# auto_threader.net
KiCad netlist of a schematic drawn in Altium Designer
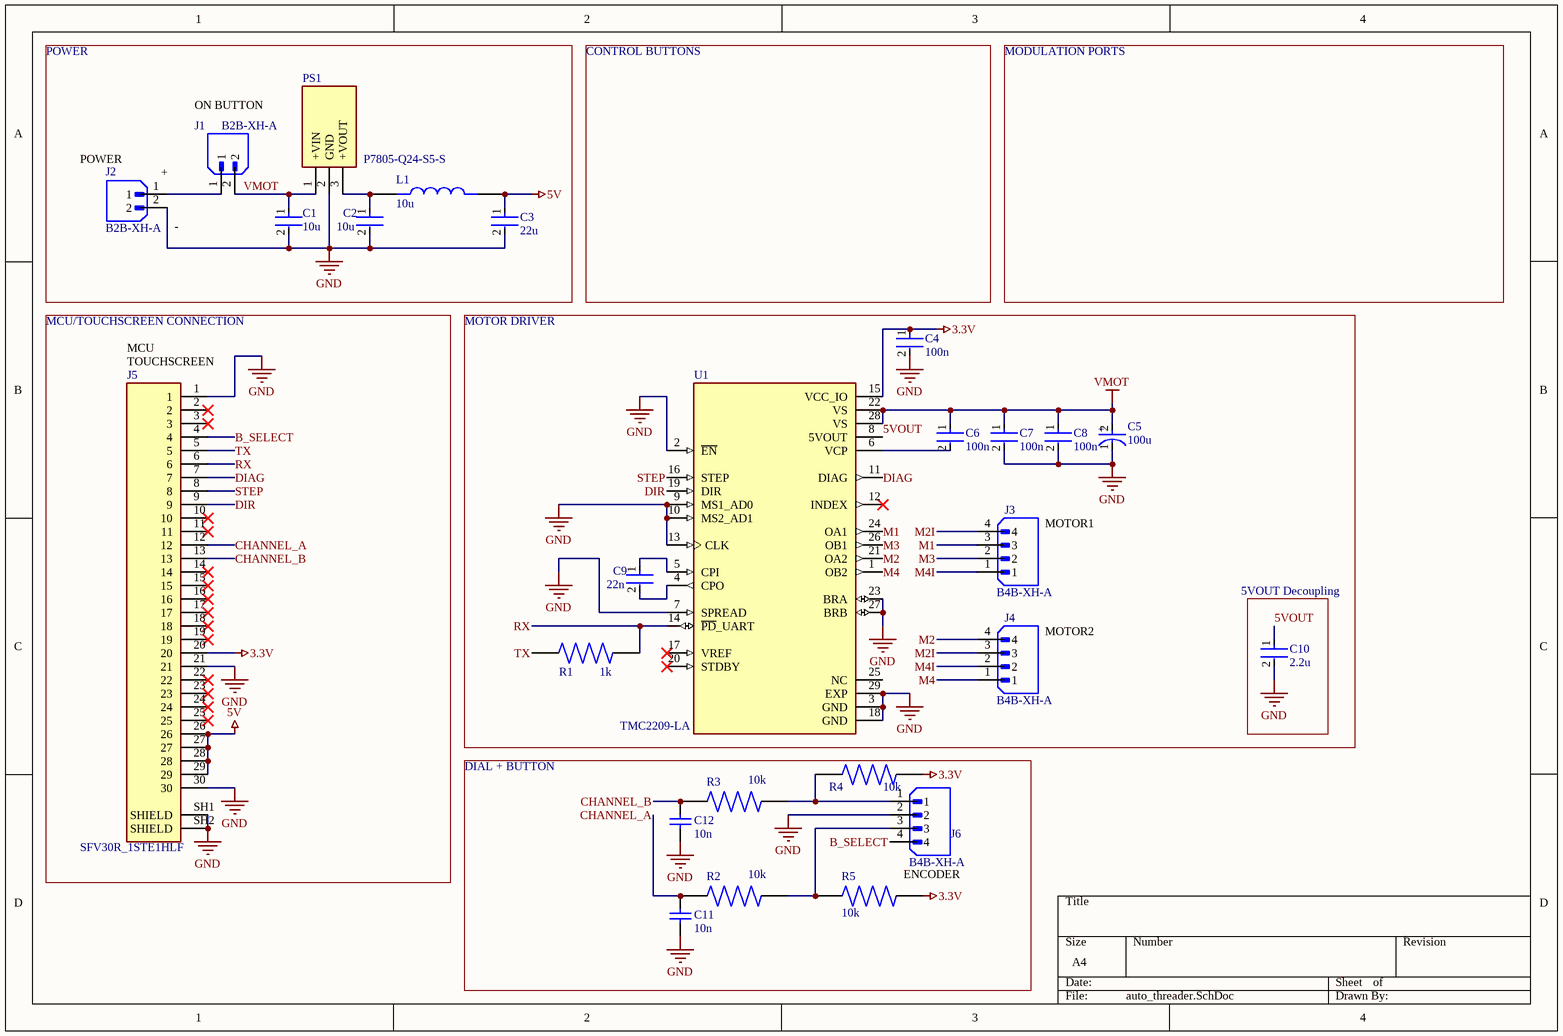
[diagram p0: auto_threader.SchDoc]

(export (version "E")
  (design (tool "Eeschema 10.0.6"))
  (components
    (comp (ref "C1")
      (value "10u")
      (footprint "GRM21BR61H106KE43L")
      (description "50V 10uF X5R ±10% 0805 Multilayer Ceramic Capacitors MLCC - SMD/SMT ROHS")
      (fields
        (field (name "MANUFACTURER") "Murata")
        (field (name "MANUFACTURER PART NUMBER") "GRM21BR61H106KE43L")
      )
      (libsource (lib "auto_threader_lib") (part "GRM21BR61H106KE43L"))
    )
    (comp (ref "C2")
      (value "10u")
      (footprint "GRM21BR71A106KA73L")
      (description "Chip Multilayer Ceramic Capacitors for General Purpose, 0805, 10uF, X7R, 15%, 10%, 10V")
      (fields (field (name "TOLERANCE") "10%"))
      (libsource (lib "auto_threader_lib") (part "GRM21BR71A106KA73L"))
    )
    (comp (ref "C3")
      (value "22u")
      (footprint "GRM188R61A226ME15D")
      (description "10V 22uF X5R ±20% 0603 Multilayer Ceramic Capacitors MLCC - SMD/SMT ROHS")
      (fields
        (field (name "MANUFACTURER") "Murata")
        (field (name "MANUFACTURER PART NUMBER") "GRM188R61A226ME15D")
      )
      (libsource (lib "auto_threader_lib") (part "GRM188R61A226ME15D"))
    )
    (comp (ref "C4")
      (value "100n")
      (footprint "CC0805KRX7R9BB104")
      (description "50V 100nF X7R ±10% 0805 Multilayer Ceramic Capacitors MLCC - SMD/SMT ROHS")
      (fields
        (field (name "MANUFACTURER") "Yageo Group")
        (field (name "MANUFACTURER PART NUMBER") "CC0805KRX7R9BB104")
      )
      (libsource (lib "auto_threader_lib") (part "CC0805KRX7R9BB104"))
    )
    (comp (ref "C5")
      (value "100u")
      (footprint "35ZLH100MEFC6.3X11")
      (description "Aluminum Electrolytic Capacitors-DIP DIP, D6.3xL11mm 100μF ±20% 35V 94mΩ 540mA 6000Hrs@105℃")
      (fields
        (field (name "MANUFACTURER") "Rubycon")
        (field (name "MANUFACTURER PART NUMBER") "35ZLH100MEFC6.3X11")
      )
      (libsource (lib "auto_threader_lib") (part "35ZLH100MEFC6.3X11"))
    )
    (comp (ref "C6")
      (value "100n")
      (footprint "CC0805KRX7R9BB104")
      (description "50V 100nF X7R ±10% 0805 Multilayer Ceramic Capacitors MLCC - SMD/SMT ROHS")
      (fields
        (field (name "MANUFACTURER") "Yageo Group")
        (field (name "MANUFACTURER PART NUMBER") "CC0805KRX7R9BB104")
      )
      (libsource (lib "auto_threader_lib") (part "CC0805KRX7R9BB104"))
    )
    (comp (ref "C7")
      (value "100n")
      (footprint "CC0805KRX7R9BB104")
      (description "50V 100nF X7R ±10% 0805 Multilayer Ceramic Capacitors MLCC - SMD/SMT ROHS")
      (fields
        (field (name "MANUFACTURER") "Yageo Group")
        (field (name "MANUFACTURER PART NUMBER") "CC0805KRX7R9BB104")
      )
      (libsource (lib "auto_threader_lib") (part "CC0805KRX7R9BB104"))
    )
    (comp (ref "C8")
      (value "100n")
      (footprint "CC0805KRX7R9BB104")
      (description "50V 100nF X7R ±10% 0805 Multilayer Ceramic Capacitors MLCC - SMD/SMT ROHS")
      (fields
        (field (name "MANUFACTURER") "Yageo Group")
        (field (name "MANUFACTURER PART NUMBER") "CC0805KRX7R9BB104")
      )
      (libsource (lib "auto_threader_lib") (part "CC0805KRX7R9BB104"))
    )
    (comp (ref "C9")
      (value "22n")
      (footprint "CC0603KRX7R9BB223")
      (description "Surface Mount Ceramic Multilayer Capacitor 0.022uF 10% X7R 50V 0603 Paper T/R")
      (fields
        (field (name "MANUFACTURER") "Yageo Group")
        (field (name "MANUFACTURER PART NUMBER") "CC0603KRX7R9BB223")
      )
      (libsource (lib "auto_threader_lib") (part "CC0603KRX7R9BB223"))
    )
    (comp (ref "C10")
      (value "2.2u")
      (footprint "GRM155C80J225KE95D")
      (description "6.3V 2.2uF X6S ±10% 0402 Multilayer Ceramic Capacitors MLCC - SMD/SMT ROHS")
      (fields
        (field (name "MANUFACTURER") "Murata")
        (field (name "MANUFACTURER PART NUMBER") "GRM155C80J225KE95D")
      )
      (libsource (lib "auto_threader_lib") (part "GRM155C80J225KE95D"))
    )
    (comp (ref "C11")
      (value "10n")
      (footprint "GCM188R71H103KA37D")
      (description "50V 10nF X7R ±10% 0603 Multilayer Ceramic Capacitors MLCC - SMD/SMT ROHS")
      (fields
        (field (name "MANUFACTURER") "Murata")
        (field (name "MANUFACTURER PART NUMBER") "GCM188R71H103KA37D")
      )
      (libsource (lib "auto_threader_lib") (part "GCM188R71H103KA37D"))
    )
    (comp (ref "C12")
      (value "10n")
      (footprint "GCM188R71H103KA37D")
      (description "50V 10nF X7R ±10% 0603 Multilayer Ceramic Capacitors MLCC - SMD/SMT ROHS")
      (fields
        (field (name "MANUFACTURER") "Murata")
        (field (name "MANUFACTURER PART NUMBER") "GCM188R71H103KA37D")
      )
      (libsource (lib "auto_threader_lib") (part "GCM188R71H103KA37D"))
    )
    (comp (ref "J1")
      (value "B2B-XH-A")
      (footprint "B2B-XH-A")
      (description "To ON BUTTON")
      (libsource (lib "auto_threader_lib") (part "B2B-XH-A"))
    )
    (comp (ref "J2")
      (value "B2B-XH-A")
      (footprint "B2B-XH-A")
      (description "To POWER")
      (libsource (lib "") (part "B2B-XH-A_1"))
    )
    (comp (ref "J3")
      (value "B4B-XH-A")
      (footprint "B4B-XH-A")
      (description "To MOTOR COILS")
      (libsource (lib "auto_threader_lib") (part "B4B-XH-A"))
    )
    (comp (ref "J4")
      (value "B4B-XH-A")
      (footprint "B4B-XH-A")
      (description "To MOTOR COILS")
      (libsource (lib "auto_threader_lib") (part "B4B-XH-A"))
    )
    (comp (ref "J5")
      (value "SFV30R_1STE1HLF")
      (footprint "SFV30R-1STE1HLF")
      (libsource (lib "auto_threader_lib") (part "SFV30R_1STE1HLF"))
    )
    (comp (ref "J6")
      (value "B4B-XH-A")
      (footprint "B4B-XH-A")
      (description "To MOTOR COILS")
      (libsource (lib "") (part "B4B-XH-A_1"))
    )
    (comp (ref "L1")
      (value "10u")
      (footprint "SRP4020TA-100M")
      (description "Ind Power Shielded Wirewound 10uH 20% 100KHz Carbonyl Powder 1.8A T/R")
      (fields
        (field (name "MANUFACTURER") "Bourns")
        (field (name "MANUFACTURER PART NUMBER") "SRP4020TA-100M")
      )
      (libsource (lib "auto_threader_lib") (part "SRP4020TA-100M"))
    )
    (comp (ref "PS1")
      (value "P7805-Q24-S5-S")
      (footprint "P7805-Q24-S5-S")
      (libsource (lib "auto_threader_lib") (part "P7805-Q24-S5-S"))
    )
    (comp (ref "R1")
      (value "1k")
      (footprint "RC0805FR-071KL")
      (description "Yageo RC0805FR-071KL SMD Resistor 0603 1k Ohm ±1% Thick Film")
      (fields
        (field (name "MANUFACTURER") "Yageo Group")
        (field (name "MANUFACTURER PART NUMBER") "RC0805FR-071KL")
      )
      (libsource (lib "auto_threader_lib") (part "RC0805FR-071KL"))
    )
    (comp (ref "R2")
      (value "10k")
      (footprint "RC0805FR-0710KL")
      (description "Res General Purpose Thick Film 0805 10k Ohm 1% 1/8W ±100ppm/°C Ceramic Paper T/R")
      (fields
        (field (name "MANUFACTURER") "Yageo Group")
        (field (name "MANUFACTURER PART NUMBER") "RC0805FR-0710KL")
      )
      (libsource (lib "auto_threader_lib") (part "RC0805FR-0710KL"))
    )
    (comp (ref "R3")
      (value "10k")
      (footprint "RC0805FR-0710KL")
      (description "Res General Purpose Thick Film 0805 10k Ohm 1% 1/8W ±100ppm/°C Ceramic Paper T/R")
      (fields
        (field (name "MANUFACTURER") "Yageo Group")
        (field (name "MANUFACTURER PART NUMBER") "RC0805FR-0710KL")
      )
      (libsource (lib "auto_threader_lib") (part "RC0805FR-0710KL"))
    )
    (comp (ref "R4")
      (value "10k")
      (footprint "RC0805FR-0710KL")
      (description "Res General Purpose Thick Film 0805 10k Ohm 1% 1/8W ±100ppm/°C Ceramic Paper T/R")
      (fields
        (field (name "MANUFACTURER") "Yageo Group")
        (field (name "MANUFACTURER PART NUMBER") "RC0805FR-0710KL")
      )
      (libsource (lib "auto_threader_lib") (part "RC0805FR-0710KL"))
    )
    (comp (ref "R5")
      (value "10k")
      (footprint "RC0805FR-0710KL")
      (description "Res General Purpose Thick Film 0805 10k Ohm 1% 1/8W ±100ppm/°C Ceramic Paper T/R")
      (fields
        (field (name "MANUFACTURER") "Yageo Group")
        (field (name "MANUFACTURER PART NUMBER") "RC0805FR-0710KL")
      )
      (libsource (lib "auto_threader_lib") (part "RC0805FR-0710KL"))
    )
    (comp (ref "U1")
      (value "TMC2209-LA")
      (footprint "TMC2209-LA")
      (libsource (lib "auto_threader_lib") (part "TMC2209-LA"))
    )
  )
  (nets
    (net (code "1") (name "/5VOUT") (class "Default")
      (node (ref "C10") (pin "1") (pinfunction "1_1") (pintype "passive"))
      (node (ref "U1") (pin "8") (pinfunction "5VOUT_8") (pintype "power_in"))
    )
    (net (code "2") (name "/B_SELECT") (class "Default")
      (node (ref "J5") (pin "4") (pinfunction "4_4") (pintype "passive"))
      (node (ref "J6") (pin "4") (pinfunction "4_4") (pintype "passive"))
    )
    (net (code "3") (name "/CHANNEL_A") (class "Default")
      (node (ref "C11") (pin "1") (pinfunction "1_1") (pintype "passive"))
      (node (ref "J5") (pin "12") (pinfunction "12_12") (pintype "passive"))
      (node (ref "R2") (pin "1") (pinfunction "1_1") (pintype "passive"))
    )
    (net (code "4") (name "/CHANNEL_B") (class "Default")
      (node (ref "C12") (pin "1") (pinfunction "1_1") (pintype "passive"))
      (node (ref "J5") (pin "13") (pinfunction "13_13") (pintype "passive"))
      (node (ref "R3") (pin "1") (pinfunction "1_1") (pintype "passive"))
    )
    (net (code "5") (name "/DIAG") (class "Default")
      (node (ref "J5") (pin "7") (pinfunction "7_7") (pintype "passive"))
      (node (ref "U1") (pin "11") (pinfunction "DIAG_11") (pintype "output"))
    )
    (net (code "6") (name "/DIR") (class "Default")
      (node (ref "J5") (pin "9") (pinfunction "9_9") (pintype "passive"))
      (node (ref "U1") (pin "19") (pinfunction "DIR_19") (pintype "input"))
    )
    (net (code "7") (name "/M1") (class "Default")
      (node (ref "J3") (pin "3") (pinfunction "3_3") (pintype "passive"))
      (node (ref "U1") (pin "24") (pinfunction "OA1_24") (pintype "output"))
    )
    (net (code "8") (name "/M2") (class "Default")
      (node (ref "J4") (pin "4") (pinfunction "4_4") (pintype "passive"))
      (node (ref "U1") (pin "21") (pinfunction "OA2_21") (pintype "output"))
    )
    (net (code "9") (name "/M2I") (class "Default")
      (node (ref "J3") (pin "4") (pinfunction "4_4") (pintype "passive"))
      (node (ref "J4") (pin "3") (pinfunction "3_3") (pintype "passive"))
    )
    (net (code "10") (name "/M3") (class "Default")
      (node (ref "J3") (pin "2") (pinfunction "2_2") (pintype "passive"))
      (node (ref "U1") (pin "26") (pinfunction "OB1_26") (pintype "output"))
    )
    (net (code "11") (name "/M4") (class "Default")
      (node (ref "J4") (pin "1") (pinfunction "1_1") (pintype "passive"))
      (node (ref "U1") (pin "1") (pinfunction "OB2_1") (pintype "output"))
    )
    (net (code "12") (name "/M4I") (class "Default")
      (node (ref "J3") (pin "1") (pinfunction "1_1") (pintype "passive"))
      (node (ref "J4") (pin "2") (pinfunction "2_2") (pintype "passive"))
    )
    (net (code "13") (name "/RX") (class "Default")
      (node (ref "J5") (pin "6") (pinfunction "6_6") (pintype "passive"))
      (node (ref "R1") (pin "2") (pinfunction "2_2") (pintype "passive"))
      (node (ref "U1") (pin "14") (pinfunction "~{PD}_UART_14") (pintype "bidirectional"))
    )
    (net (code "14") (name "/STEP") (class "Default")
      (node (ref "J5") (pin "8") (pinfunction "8_8") (pintype "passive"))
      (node (ref "U1") (pin "16") (pinfunction "STEP_16") (pintype "input"))
    )
    (net (code "15") (name "/TX") (class "Default")
      (node (ref "J5") (pin "5") (pinfunction "5_5") (pintype "passive"))
      (node (ref "R1") (pin "1") (pinfunction "1_1") (pintype "passive"))
    )
    (net (code "16") (name "3.3V") (class "Default")
      (node (ref "C4") (pin "1") (pinfunction "1_1") (pintype "passive"))
      (node (ref "J5") (pin "20") (pinfunction "20_20") (pintype "passive"))
      (node (ref "R4") (pin "2") (pinfunction "2_2") (pintype "passive"))
      (node (ref "R5") (pin "2") (pinfunction "2_2") (pintype "passive"))
      (node (ref "U1") (pin "15") (pinfunction "VCC_IO_15") (pintype "power_in"))
    )
    (net (code "17") (name "5V") (class "Default")
      (node (ref "C3") (pin "1") (pinfunction "1_1") (pintype "passive"))
      (node (ref "J5") (pin "26") (pinfunction "26_26") (pintype "passive"))
      (node (ref "J5") (pin "27") (pinfunction "27_27") (pintype "passive"))
      (node (ref "J5") (pin "28") (pinfunction "28_28") (pintype "passive"))
      (node (ref "J5") (pin "29") (pinfunction "29_29") (pintype "passive"))
      (node (ref "L1") (pin "2") (pinfunction "2_2") (pintype "passive"))
    )
    (net (code "18") (name "GND") (class "Default")
      (node (ref "C1") (pin "2") (pinfunction "2_2") (pintype "passive"))
      (node (ref "C10") (pin "2") (pinfunction "2_2") (pintype "passive"))
      (node (ref "C11") (pin "2") (pinfunction "2_2") (pintype "passive"))
      (node (ref "C12") (pin "2") (pinfunction "2_2") (pintype "passive"))
      (node (ref "C2") (pin "2") (pinfunction "2_2") (pintype "passive"))
      (node (ref "C3") (pin "2") (pinfunction "2_2") (pintype "passive"))
      (node (ref "C4") (pin "2") (pinfunction "2_2") (pintype "passive"))
      (node (ref "C5") (pin "1") (pinfunction "C_1") (pintype "passive"))
      (node (ref "C7") (pin "2") (pinfunction "2_2") (pintype "passive"))
      (node (ref "C8") (pin "2") (pinfunction "2_2") (pintype "passive"))
      (node (ref "J2") (pin "2") (pinfunction "2_2") (pintype "passive"))
      (node (ref "J5") (pin "1") (pinfunction "1_1") (pintype "passive"))
      (node (ref "J5") (pin "21") (pinfunction "21_21") (pintype "passive"))
      (node (ref "J5") (pin "30") (pinfunction "30_30") (pintype "passive"))
      (node (ref "J5") (pin "SH1") (pinfunction "SHIELD_SH1") (pintype "passive"))
      (node (ref "J5") (pin "SH2") (pinfunction "SHIELD_SH2") (pintype "passive"))
      (node (ref "J6") (pin "2") (pinfunction "2_2") (pintype "passive"))
      (node (ref "PS1") (pin "2") (pinfunction "GND_2") (pintype "passive"))
      (node (ref "U1") (pin "10") (pinfunction "MS2_AD1_10") (pintype "input"))
      (node (ref "U1") (pin "13") (pinfunction "CLK_13") (pintype "input"))
      (node (ref "U1") (pin "18") (pinfunction "GND_18") (pintype "power_in"))
      (node (ref "U1") (pin "2") (pinfunction "~{EN}_2") (pintype "input"))
      (node (ref "U1") (pin "23") (pinfunction "BRA_23") (pintype "bidirectional"))
      (node (ref "U1") (pin "27") (pinfunction "BRB_27") (pintype "bidirectional"))
      (node (ref "U1") (pin "29") (pinfunction "EXP_29") (pintype "power_in"))
      (node (ref "U1") (pin "3") (pinfunction "GND_3") (pintype "power_in"))
      (node (ref "U1") (pin "7") (pinfunction "SPREAD_7") (pintype "input"))
      (node (ref "U1") (pin "9") (pinfunction "MS1_AD0_9") (pintype "input"))
    )
    (net (code "19") (name "Net-(J1-Pad1)") (class "Default")
      (node (ref "J1") (pin "1") (pinfunction "1_1") (pintype "passive"))
      (node (ref "J2") (pin "1") (pinfunction "1_1") (pintype "passive"))
    )
    (net (code "20") (name "Net-(J6-Pad1)") (class "Default")
      (node (ref "J6") (pin "1") (pinfunction "1_1") (pintype "passive"))
      (node (ref "R3") (pin "2") (pinfunction "2_2") (pintype "passive"))
      (node (ref "R4") (pin "1") (pinfunction "1_1") (pintype "passive"))
    )
    (net (code "21") (name "Net-(J6-Pad3)") (class "Default")
      (node (ref "J6") (pin "3") (pinfunction "3_3") (pintype "passive"))
      (node (ref "R2") (pin "2") (pinfunction "2_2") (pintype "passive"))
      (node (ref "R5") (pin "1") (pinfunction "1_1") (pintype "passive"))
    )
    (net (code "22") (name "Net-(PS1-+VOUT)") (class "Default")
      (node (ref "C2") (pin "1") (pinfunction "1_1") (pintype "passive"))
      (node (ref "L1") (pin "1") (pinfunction "1_1") (pintype "passive"))
      (node (ref "PS1") (pin "3") (pinfunction "+VOUT_3") (pintype "passive"))
    )
    (net (code "23") (name "Net-(U1-CPI)") (class "Default")
      (node (ref "C9") (pin "1") (pinfunction "1_1") (pintype "passive"))
      (node (ref "U1") (pin "5") (pinfunction "CPI_5") (pintype "input"))
    )
    (net (code "24") (name "Net-(U1-CPO)") (class "Default")
      (node (ref "C9") (pin "2") (pinfunction "2_2") (pintype "passive"))
      (node (ref "U1") (pin "4") (pinfunction "CPO_4") (pintype "output"))
    )
    (net (code "25") (name "Net-(U1-VCP)") (class "Default")
      (node (ref "C6") (pin "2") (pinfunction "2_2") (pintype "passive"))
      (node (ref "U1") (pin "6") (pinfunction "VCP_6") (pintype "power_in"))
    )
    (net (code "26") (name "VMOT") (class "Default")
      (node (ref "C1") (pin "1") (pinfunction "1_1") (pintype "passive"))
      (node (ref "C5") (pin "2") (pinfunction "A_2") (pintype "passive"))
      (node (ref "C6") (pin "1") (pinfunction "1_1") (pintype "passive"))
      (node (ref "C7") (pin "1") (pinfunction "1_1") (pintype "passive"))
      (node (ref "C8") (pin "1") (pinfunction "1_1") (pintype "passive"))
      (node (ref "J1") (pin "2") (pinfunction "2_2") (pintype "passive"))
      (node (ref "PS1") (pin "1") (pinfunction "+VIN_1") (pintype "passive"))
      (node (ref "U1") (pin "22") (pinfunction "VS_22") (pintype "power_in"))
      (node (ref "U1") (pin "28") (pinfunction "VS_28") (pintype "power_in"))
    )
    (net (code "27") (name "unconnected-(J5-Pad2)") (class "Default")
      (node (ref "J5") (pin "2") (pinfunction "2_2") (pintype "passive+no_connect"))
    )
    (net (code "28") (name "unconnected-(J5-Pad3)") (class "Default")
      (node (ref "J5") (pin "3") (pinfunction "3_3") (pintype "passive+no_connect"))
    )
    (net (code "29") (name "unconnected-(J5-Pad10)") (class "Default")
      (node (ref "J5") (pin "10") (pinfunction "10_10") (pintype "passive+no_connect"))
    )
    (net (code "30") (name "unconnected-(J5-Pad11)") (class "Default")
      (node (ref "J5") (pin "11") (pinfunction "11_11") (pintype "passive+no_connect"))
    )
    (net (code "31") (name "unconnected-(J5-Pad14)") (class "Default")
      (node (ref "J5") (pin "14") (pinfunction "14_14") (pintype "passive+no_connect"))
    )
    (net (code "32") (name "unconnected-(J5-Pad15)") (class "Default")
      (node (ref "J5") (pin "15") (pinfunction "15_15") (pintype "passive+no_connect"))
    )
    (net (code "33") (name "unconnected-(J5-Pad16)") (class "Default")
      (node (ref "J5") (pin "16") (pinfunction "16_16") (pintype "passive+no_connect"))
    )
    (net (code "34") (name "unconnected-(J5-Pad17)") (class "Default")
      (node (ref "J5") (pin "17") (pinfunction "17_17") (pintype "passive+no_connect"))
    )
    (net (code "35") (name "unconnected-(J5-Pad18)") (class "Default")
      (node (ref "J5") (pin "18") (pinfunction "18_18") (pintype "passive+no_connect"))
    )
    (net (code "36") (name "unconnected-(J5-Pad19)") (class "Default")
      (node (ref "J5") (pin "19") (pinfunction "19_19") (pintype "passive+no_connect"))
    )
    (net (code "37") (name "unconnected-(J5-Pad22)") (class "Default")
      (node (ref "J5") (pin "22") (pinfunction "22_22") (pintype "passive+no_connect"))
    )
    (net (code "38") (name "unconnected-(J5-Pad23)") (class "Default")
      (node (ref "J5") (pin "23") (pinfunction "23_23") (pintype "passive+no_connect"))
    )
    (net (code "39") (name "unconnected-(J5-Pad24)") (class "Default")
      (node (ref "J5") (pin "24") (pinfunction "24_24") (pintype "passive+no_connect"))
    )
    (net (code "40") (name "unconnected-(J5-Pad25)") (class "Default")
      (node (ref "J5") (pin "25") (pinfunction "25_25") (pintype "passive+no_connect"))
    )
    (net (code "41") (name "unconnected-(U1-INDEX-Pad12)") (class "Default")
      (node (ref "U1") (pin "12") (pinfunction "INDEX_12") (pintype "output+no_connect"))
    )
    (net (code "42") (name "unconnected-(U1-NC-Pad25)") (class "Default")
      (node (ref "U1") (pin "25") (pinfunction "NC_25") (pintype "passive"))
    )
    (net (code "43") (name "unconnected-(U1-STDBY-Pad20)") (class "Default")
      (node (ref "U1") (pin "20") (pinfunction "STDBY_20") (pintype "input+no_connect"))
    )
    (net (code "44") (name "unconnected-(U1-VREF-Pad17)") (class "Default")
      (node (ref "U1") (pin "17") (pinfunction "VREF_17") (pintype "input+no_connect"))
    )
  )
)
